# 11Dof.net
KiCad netlist of a schematic drawn in EAGLE
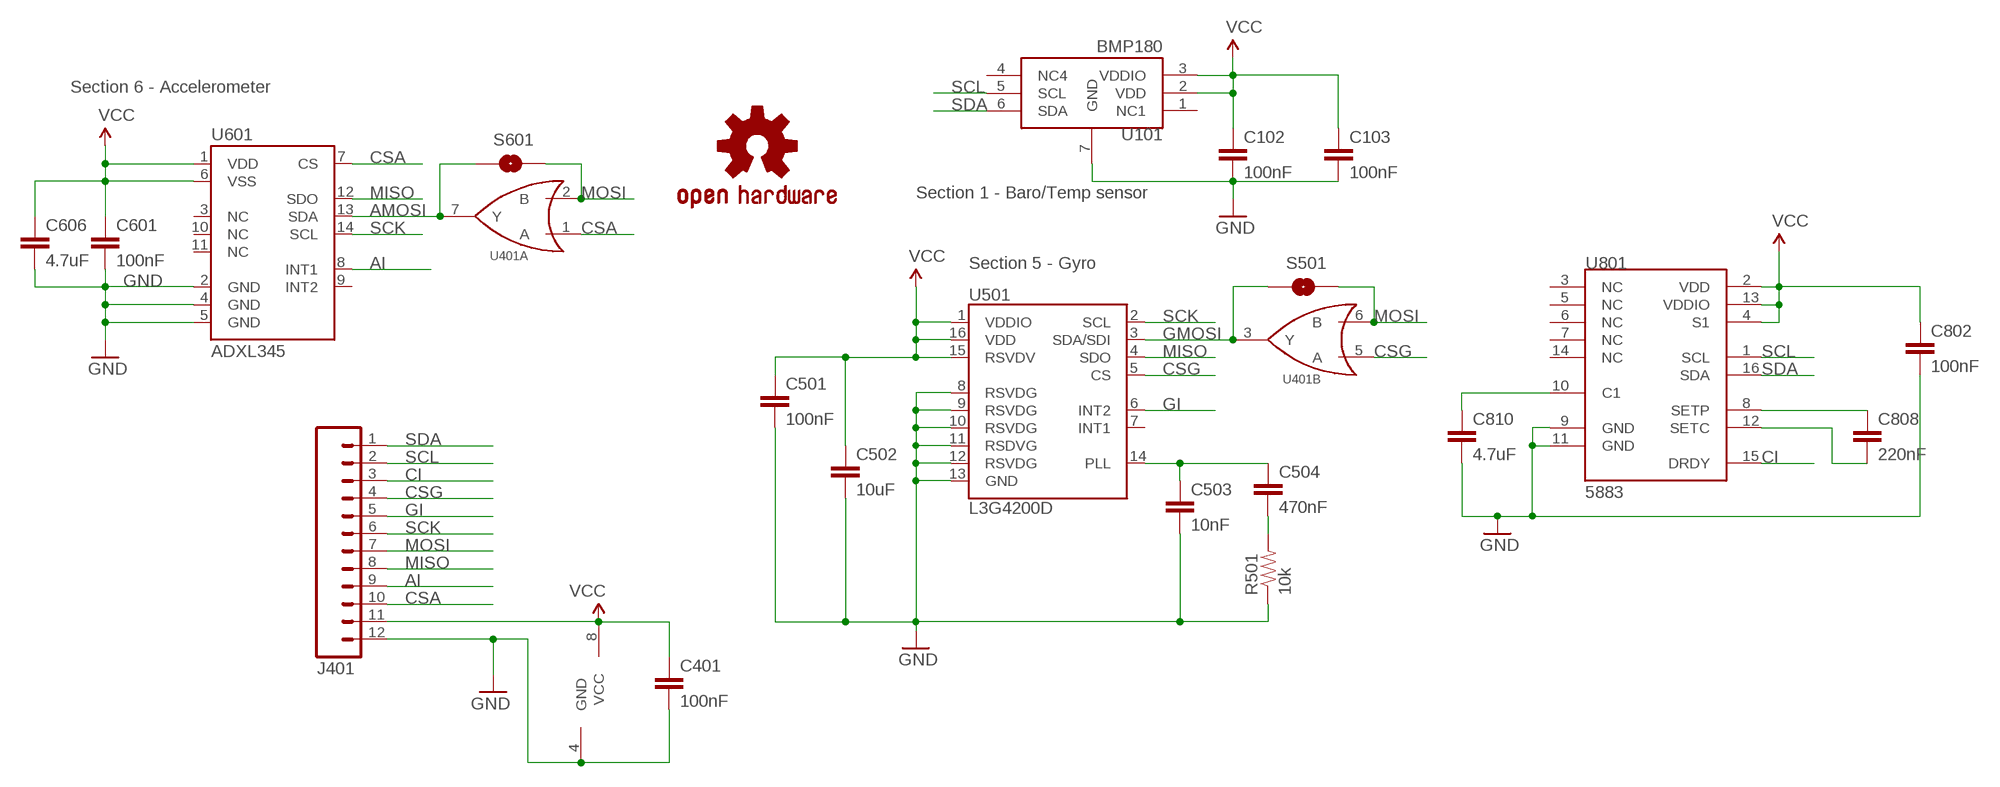
[diagram p0: schematic, sheet 1]

(export (version "E")
  (design (tool "Eeschema 10.0.6"))
  (components
    (comp (ref "C102")
      (value "100nF")
      (footprint "eagle-import:0603-CAP")
      (libsource (lib "eagle-import") (part "CAP0603-CAP"))
    )
    (comp (ref "C103")
      (value "100nF")
      (footprint "eagle-import:0603-CAP")
      (libsource (lib "eagle-import") (part "CAP0603-CAP"))
    )
    (comp (ref "C401")
      (value "100nF")
      (footprint "eagle-import:0603-CAP")
      (libsource (lib "eagle-import") (part "CAP0603-CAP"))
    )
    (comp (ref "C501")
      (value "100nF")
      (footprint "eagle-import:0603-CAP")
      (libsource (lib "eagle-import") (part "CAP0603-CAP"))
    )
    (comp (ref "C502")
      (value "10uF")
      (footprint "eagle-import:0603-CAP")
      (libsource (lib "eagle-import") (part "CAP0603-CAP"))
    )
    (comp (ref "C503")
      (value "10nF")
      (footprint "eagle-import:0603-CAP")
      (libsource (lib "eagle-import") (part "CAP0603-CAP"))
    )
    (comp (ref "C504")
      (value "470nF")
      (footprint "eagle-import:0603-CAP")
      (libsource (lib "eagle-import") (part "CAP0603-CAP"))
    )
    (comp (ref "C601")
      (value "100nF")
      (footprint "eagle-import:0603-CAP")
      (libsource (lib "eagle-import") (part "CAP0603-CAP"))
    )
    (comp (ref "C606")
      (value "4.7uF")
      (footprint "eagle-import:0603-CAP")
      (libsource (lib "eagle-import") (part "CAP0603-CAP"))
    )
    (comp (ref "C802")
      (value "100nF")
      (footprint "eagle-import:0603-CAP")
      (libsource (lib "eagle-import") (part "CAP0603-CAP"))
    )
    (comp (ref "C808")
      (value "220nF")
      (footprint "eagle-import:0603-CAP")
      (libsource (lib "eagle-import") (part "CAP0603-CAP"))
    )
    (comp (ref "C810")
      (value "4.7uF")
      (footprint "eagle-import:0603-CAP")
      (libsource (lib "eagle-import") (part "CAP0603-CAP"))
    )
    (comp (ref "J401")
      (value "M12PTH")
      (footprint "eagle-import:1X12")
      (libsource (lib "eagle-import") (part "M12PTH"))
    )
    (comp (ref "R501")
      (value "10k")
      (footprint "eagle-import:0603-RES")
      (libsource (lib "eagle-import") (part "RESISTOR0603-RES"))
    )
    (comp (ref "S501")
      (value "SOLDERJUMPERNO")
      (footprint "eagle-import:SJ_2S-NO")
      (libsource (lib "eagle-import") (part "SOLDERJUMPERNO"))
    )
    (comp (ref "S601")
      (value "SOLDERJUMPERNO")
      (footprint "eagle-import:SJ_2S-NO")
      (libsource (lib "eagle-import") (part "SOLDERJUMPERNO"))
    )
    (comp (ref "U$2")
      (value "OSHW-LOGOS")
      (footprint "eagle-import:OSHW-LOGO-S")
      (libsource (lib "eagle-import") (part "OSHW-LOGOS"))
    )
    (comp (ref "U101")
      (value "BMP180")
      (footprint "eagle-import:BMP180")
      (libsource (lib "eagle-import") (part "BMP180"))
    )
    (comp (ref "U401")
      (value "7432")
      (footprint "eagle-import:DCU_8")
      (fields (field (name "DIGIKEY") "296-13268-1-ND"))
      (libsource (lib "eagle-import") (part "SN74LVC2G32"))
    )
    (comp (ref "U501")
      (value "L3G4200D")
      (footprint "eagle-import:LGA16-4X4")
      (libsource (lib "eagle-import") (part "L3G4200D"))
    )
    (comp (ref "U601")
      (value "ADXL345")
      (footprint "eagle-import:LGA14")
      (libsource (lib "eagle-import") (part "ADXL345"))
    )
    (comp (ref "U801")
      (value "5883")
      (footprint "eagle-import:16LPCC")
      (libsource (lib "eagle-import") (part "HMC5883LSMD"))
    )
  )
  (nets
    (net (code "1") (name "/AI") (class "Default")
      (node (ref "J401") (pin "9") (pinfunction "9_9") (pintype "passive"))
      (node (ref "U601") (pin "8") (pinfunction "INT1_8") (pintype "bidirectional"))
    )
    (net (code "2") (name "/AMOSI") (class "Default")
      (node (ref "S601") (pin "1") (pinfunction "1_1") (pintype "passive"))
      (node (ref "U401") (pin "7") (pinfunction "Y_7") (pintype "bidirectional"))
      (node (ref "U601") (pin "13") (pinfunction "SDA_13") (pintype "bidirectional"))
    )
    (net (code "3") (name "/CI") (class "Default")
      (node (ref "J401") (pin "3") (pinfunction "3_3") (pintype "passive"))
      (node (ref "U801") (pin "15") (pinfunction "DRDY_15") (pintype "bidirectional"))
    )
    (net (code "4") (name "/CSA") (class "Default")
      (node (ref "J401") (pin "10") (pinfunction "10_10") (pintype "passive"))
      (node (ref "U401") (pin "1") (pinfunction "A_1") (pintype "bidirectional"))
      (node (ref "U601") (pin "7") (pinfunction "CS_7") (pintype "bidirectional"))
    )
    (net (code "5") (name "/CSG") (class "Default")
      (node (ref "J401") (pin "4") (pinfunction "4_4") (pintype "passive"))
      (node (ref "U401") (pin "5") (pinfunction "A_5") (pintype "bidirectional"))
      (node (ref "U501") (pin "5") (pinfunction "CS_5") (pintype "bidirectional"))
    )
    (net (code "6") (name "/GI") (class "Default")
      (node (ref "J401") (pin "5") (pinfunction "5_5") (pintype "passive"))
      (node (ref "U501") (pin "6") (pinfunction "INT2_6") (pintype "bidirectional"))
    )
    (net (code "7") (name "/GMOSI") (class "Default")
      (node (ref "S501") (pin "1") (pinfunction "1_1") (pintype "passive"))
      (node (ref "U401") (pin "3") (pinfunction "Y_3") (pintype "bidirectional"))
      (node (ref "U501") (pin "3") (pinfunction "SDA/SDI_3") (pintype "bidirectional"))
    )
    (net (code "8") (name "/MISO") (class "Default")
      (node (ref "J401") (pin "8") (pinfunction "8_8") (pintype "passive"))
      (node (ref "U501") (pin "4") (pinfunction "SDO_4") (pintype "bidirectional"))
      (node (ref "U601") (pin "12") (pinfunction "SDO_12") (pintype "bidirectional"))
    )
    (net (code "9") (name "/MOSI") (class "Default")
      (node (ref "J401") (pin "7") (pinfunction "7_7") (pintype "passive"))
      (node (ref "S501") (pin "2") (pinfunction "2_2") (pintype "passive"))
      (node (ref "S601") (pin "2") (pinfunction "2_2") (pintype "passive"))
      (node (ref "U401") (pin "2") (pinfunction "B_2") (pintype "bidirectional"))
      (node (ref "U401") (pin "6") (pinfunction "B_6") (pintype "bidirectional"))
    )
    (net (code "10") (name "/SCK") (class "Default")
      (node (ref "J401") (pin "6") (pinfunction "6_6") (pintype "passive"))
      (node (ref "U501") (pin "2") (pinfunction "SCL_2") (pintype "bidirectional"))
      (node (ref "U601") (pin "14") (pinfunction "SCL_14") (pintype "bidirectional"))
    )
    (net (code "11") (name "/SCL") (class "Default")
      (node (ref "J401") (pin "2") (pinfunction "2_2") (pintype "passive"))
      (node (ref "U101") (pin "5") (pinfunction "SCL_5") (pintype "input"))
      (node (ref "U801") (pin "1") (pinfunction "SCL_1") (pintype "bidirectional"))
    )
    (net (code "12") (name "/SDA") (class "Default")
      (node (ref "J401") (pin "1") (pinfunction "1_1") (pintype "passive"))
      (node (ref "U101") (pin "6") (pinfunction "SDA_6") (pintype "bidirectional"))
      (node (ref "U801") (pin "16") (pinfunction "SDA_16") (pintype "bidirectional"))
    )
    (net (code "13") (name "GND") (class "Default")
      (node (ref "C102") (pin "2") (pinfunction "2_2") (pintype "passive"))
      (node (ref "C103") (pin "2") (pinfunction "2_2") (pintype "passive"))
      (node (ref "C401") (pin "2") (pinfunction "2_2") (pintype "passive"))
      (node (ref "C501") (pin "2") (pinfunction "2_2") (pintype "passive"))
      (node (ref "C502") (pin "2") (pinfunction "2_2") (pintype "passive"))
      (node (ref "C503") (pin "2") (pinfunction "2_2") (pintype "passive"))
      (node (ref "C601") (pin "2") (pinfunction "2_2") (pintype "passive"))
      (node (ref "C606") (pin "2") (pinfunction "2_2") (pintype "passive"))
      (node (ref "C802") (pin "2") (pinfunction "2_2") (pintype "passive"))
      (node (ref "C810") (pin "2") (pinfunction "2_2") (pintype "passive"))
      (node (ref "J401") (pin "12") (pinfunction "12_12") (pintype "passive"))
      (node (ref "R501") (pin "1") (pinfunction "1_1") (pintype "passive"))
      (node (ref "U101") (pin "7") (pinfunction "GND_7") (pintype "power_in"))
      (node (ref "U401") (pin "4") (pinfunction "GND_4") (pintype "bidirectional"))
      (node (ref "U501") (pin "10") (pinfunction "RSVDG_10") (pintype "bidirectional"))
      (node (ref "U501") (pin "11") (pinfunction "RSDVG_11") (pintype "bidirectional"))
      (node (ref "U501") (pin "12") (pinfunction "RSVDG_12") (pintype "bidirectional"))
      (node (ref "U501") (pin "13") (pinfunction "GND_13") (pintype "bidirectional"))
      (node (ref "U501") (pin "8") (pinfunction "RSVDG_8") (pintype "bidirectional"))
      (node (ref "U501") (pin "9") (pinfunction "RSVDG_9") (pintype "bidirectional"))
      (node (ref "U601") (pin "2") (pinfunction "GND_2") (pintype "bidirectional"))
      (node (ref "U601") (pin "4") (pinfunction "GND_4") (pintype "bidirectional"))
      (node (ref "U601") (pin "5") (pinfunction "GND_5") (pintype "bidirectional"))
      (node (ref "U801") (pin "11") (pinfunction "GND_11") (pintype "bidirectional"))
      (node (ref "U801") (pin "9") (pinfunction "GND_9") (pintype "bidirectional"))
    )
    (net (code "14") (name "Net-(C504-Pad2)") (class "Default")
      (node (ref "C504") (pin "2") (pinfunction "2_2") (pintype "passive"))
      (node (ref "R501") (pin "2") (pinfunction "2_2") (pintype "passive"))
    )
    (net (code "15") (name "Net-(U501-PLL)") (class "Default")
      (node (ref "C503") (pin "1") (pinfunction "1_1") (pintype "passive"))
      (node (ref "C504") (pin "1") (pinfunction "1_1") (pintype "passive"))
      (node (ref "U501") (pin "14") (pinfunction "PLL_14") (pintype "bidirectional"))
    )
    (net (code "16") (name "Net-(U801-C1)") (class "Default")
      (node (ref "C810") (pin "1") (pinfunction "1_1") (pintype "passive"))
      (node (ref "U801") (pin "10") (pinfunction "C1_10") (pintype "bidirectional"))
    )
    (net (code "17") (name "Net-(U801-SETC)") (class "Default")
      (node (ref "C808") (pin "2") (pinfunction "2_2") (pintype "passive"))
      (node (ref "U801") (pin "12") (pinfunction "SETC_12") (pintype "bidirectional"))
    )
    (net (code "18") (name "Net-(U801-SETP)") (class "Default")
      (node (ref "C808") (pin "1") (pinfunction "1_1") (pintype "passive"))
      (node (ref "U801") (pin "8") (pinfunction "SETP_8") (pintype "bidirectional"))
    )
    (net (code "19") (name "VCC") (class "Default")
      (node (ref "C102") (pin "1") (pinfunction "1_1") (pintype "passive"))
      (node (ref "C103") (pin "1") (pinfunction "1_1") (pintype "passive"))
      (node (ref "C401") (pin "1") (pinfunction "1_1") (pintype "passive"))
      (node (ref "C501") (pin "1") (pinfunction "1_1") (pintype "passive"))
      (node (ref "C502") (pin "1") (pinfunction "1_1") (pintype "passive"))
      (node (ref "C601") (pin "1") (pinfunction "1_1") (pintype "passive"))
      (node (ref "C606") (pin "1") (pinfunction "1_1") (pintype "passive"))
      (node (ref "C802") (pin "1") (pinfunction "1_1") (pintype "passive"))
      (node (ref "J401") (pin "11") (pinfunction "11_11") (pintype "passive"))
      (node (ref "U101") (pin "2") (pinfunction "VDD_2") (pintype "power_in"))
      (node (ref "U101") (pin "3") (pinfunction "VDDIO_3") (pintype "power_in"))
      (node (ref "U401") (pin "8") (pinfunction "VCC_8") (pintype "bidirectional"))
      (node (ref "U501") (pin "1") (pinfunction "VDDIO_1") (pintype "bidirectional"))
      (node (ref "U501") (pin "15") (pinfunction "RSVDV_15") (pintype "bidirectional"))
      (node (ref "U501") (pin "16") (pinfunction "VDD_16") (pintype "bidirectional"))
      (node (ref "U601") (pin "1") (pinfunction "VDD_1") (pintype "bidirectional"))
      (node (ref "U601") (pin "6") (pinfunction "VSS_6") (pintype "bidirectional"))
      (node (ref "U801") (pin "13") (pinfunction "VDDIO_13") (pintype "bidirectional"))
      (node (ref "U801") (pin "2") (pinfunction "VDD_2") (pintype "bidirectional"))
      (node (ref "U801") (pin "4") (pinfunction "S1_4") (pintype "bidirectional"))
    )
    (net (code "20") (name "unconnected-(U101-NC1-Pad1)") (class "Default")
      (node (ref "U101") (pin "1") (pinfunction "NC1_1") (pintype "no_connect"))
    )
    (net (code "21") (name "unconnected-(U101-NC4-Pad4)") (class "Default")
      (node (ref "U101") (pin "4") (pinfunction "NC4_4") (pintype "no_connect"))
    )
    (net (code "22") (name "unconnected-(U501-INT1-Pad7)") (class "Default")
      (node (ref "U501") (pin "7") (pinfunction "INT1_7") (pintype "bidirectional"))
    )
    (net (code "23") (name "unconnected-(U601-INT2-Pad9)") (class "Default")
      (node (ref "U601") (pin "9") (pinfunction "INT2_9") (pintype "bidirectional"))
    )
    (net (code "24") (name "unconnected-(U601-NC-Pad3)") (class "Default")
      (node (ref "U601") (pin "3") (pinfunction "NC_3") (pintype "bidirectional"))
    )
    (net (code "25") (name "unconnected-(U601-NC-Pad10)") (class "Default")
      (node (ref "U601") (pin "10") (pinfunction "NC_10") (pintype "bidirectional"))
    )
    (net (code "26") (name "unconnected-(U601-NC-Pad11)") (class "Default")
      (node (ref "U601") (pin "11") (pinfunction "NC_11") (pintype "bidirectional"))
    )
    (net (code "27") (name "unconnected-(U801-NC-Pad3)") (class "Default")
      (node (ref "U801") (pin "3") (pinfunction "NC_3") (pintype "bidirectional"))
    )
    (net (code "28") (name "unconnected-(U801-NC-Pad5)") (class "Default")
      (node (ref "U801") (pin "5") (pinfunction "NC_5") (pintype "bidirectional"))
    )
    (net (code "29") (name "unconnected-(U801-NC-Pad6)") (class "Default")
      (node (ref "U801") (pin "6") (pinfunction "NC_6") (pintype "bidirectional"))
    )
    (net (code "30") (name "unconnected-(U801-NC-Pad7)") (class "Default")
      (node (ref "U801") (pin "7") (pinfunction "NC_7") (pintype "bidirectional"))
    )
    (net (code "31") (name "unconnected-(U801-NC-Pad14)") (class "Default")
      (node (ref "U801") (pin "14") (pinfunction "NC_14") (pintype "bidirectional"))
    )
  )
)
